# Sheet1.net
KiCad netlist of a schematic drawn in Altium Designer
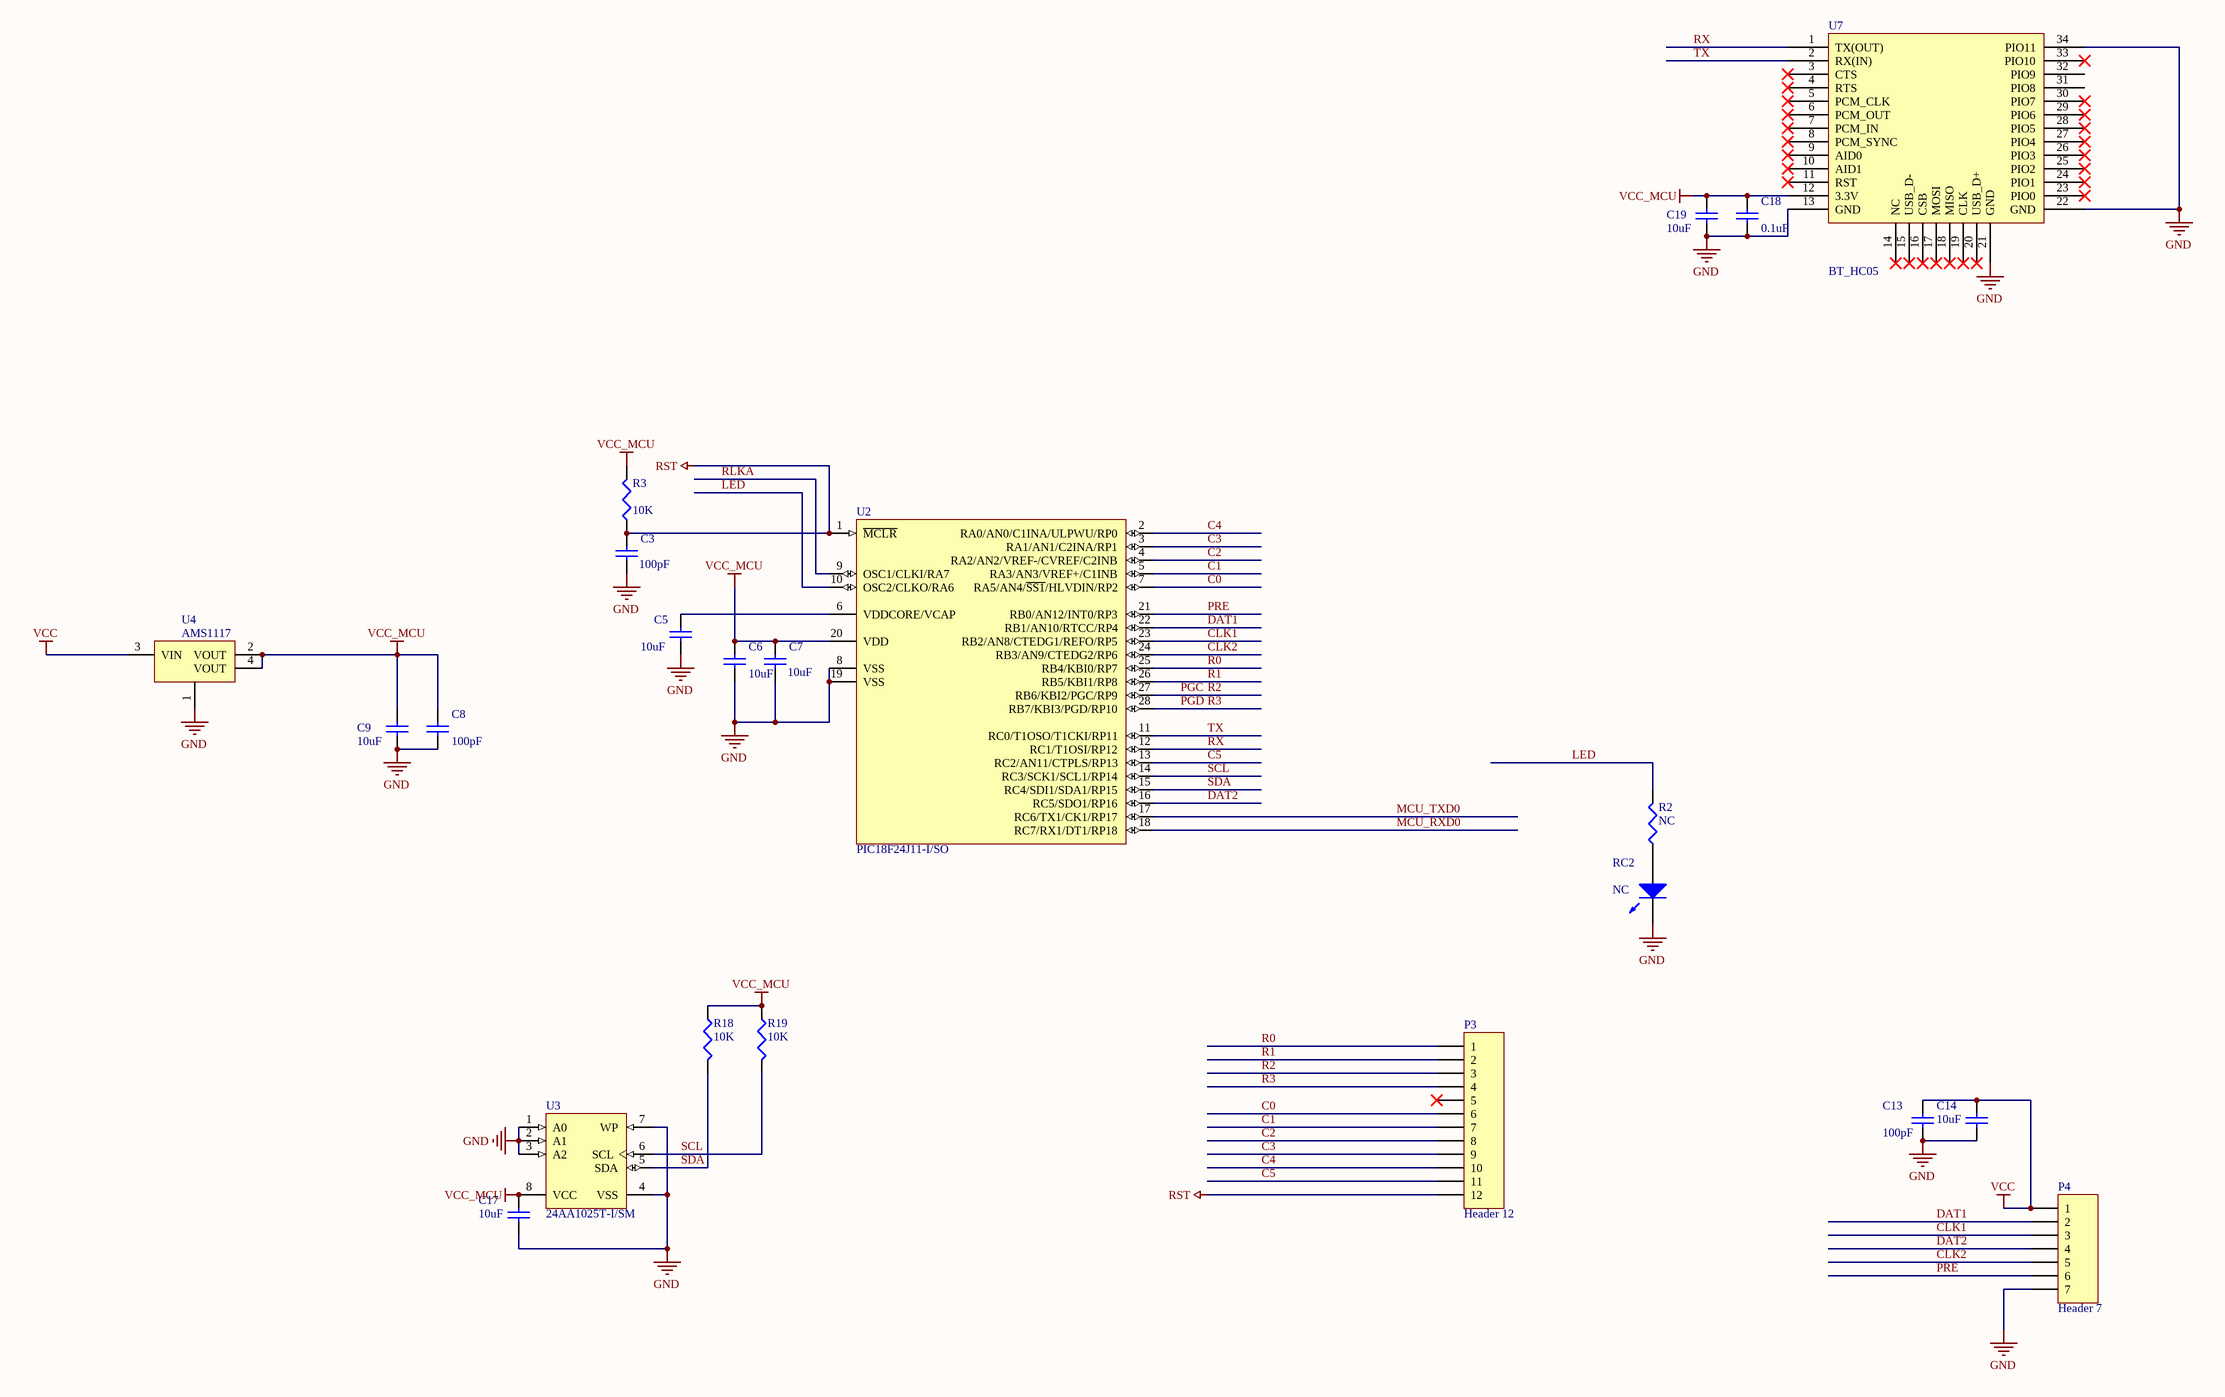
[diagram p0: Sheet1.SchDoc]

(export (version "E")
  (design (tool "Eeschema 10.0.6"))
  (components
    (comp (ref "C3")
      (value "100pF")
      (footprint "CAPC2013X05N")
      (description "0.10µF 50V Ceramic Capacitor Y5V (F) 0805 (2012 Metric) 0.079\" L x 0.049\" W (2.00mm x 1.25mm)")
      (fields (field (name "Comment") "CL21F104ZBCNNNC"))
      (libsource (lib "Miscellaneous Devices") (part "Cap Semi"))
    )
    (comp (ref "C5")
      (value "10uF")
      (footprint "CAPC2013X05N")
      (description "10µF 6.3V Ceramic Capacitor X5R 0805 (2012 Metric) 0.079\" L x 0.049\" W (2.00mm x 1.25mm)")
      (fields (field (name "Comment") "GRM219R60J106KE19D"))
      (libsource (lib "Miscellaneous Devices") (part "Cap Semi"))
    )
    (comp (ref "C6")
      (value "10uF")
      (footprint "CAPC2013X05N")
      (description "10µF 6.3V Ceramic Capacitor X5R 0805 (2012 Metric) 0.079\" L x 0.049\" W (2.00mm x 1.25mm)")
      (fields (field (name "Comment") "GRM219R60J106KE19D"))
      (libsource (lib "Miscellaneous Devices") (part "Cap Semi"))
    )
    (comp (ref "C7")
      (value "10uF")
      (footprint "CAPC2013X05N")
      (description "0.10µF 50V Cera2012 Metric) 0.079\" L x 0.049\" W (2.00mm x 1.25mm)")
      (fields (field (name "Comment") "GRM219R60J106KE19D"))
      (libsource (lib "Miscellaneous Devices") (part "Cap Semi"))
    )
    (comp (ref "C8")
      (value "100pF")
      (footprint "RESC2012L")
      (description "0.10µF 50V Ceramic Capacitor Y5V (F) 0805 (2012 Metric) 0.079\" L x 0.049\" W (2.00mm x 1.25mm)")
      (fields (field (name "Comment") "CL21F104ZBCNNNC"))
      (libsource (lib "Miscellaneous Devices") (part "Cap"))
    )
    (comp (ref "C9")
      (value "10uF")
      (footprint "RESC2012L")
      (description "10µF 6.3V Ceramic Capacitor X5R 0805 (2012 Metric) 0.079\" L x 0.049\" W (2.00mm x 1.25mm)")
      (fields (field (name "Comment") "GRM219R60J106KE19D"))
      (libsource (lib "Miscellaneous Devices") (part "Cap"))
    )
    (comp (ref "C13")
      (value "100pF")
      (footprint "RESC2012L")
      (description "0.10µF 50V Ceramic Capacitor Y5V (F) 0805 (2012 Metric) 0.079\" L x 0.049\" W (2.00mm x 1.25mm)")
      (fields (field (name "Comment") "CL21F104ZBCNNNC"))
      (libsource (lib "Miscellaneous Devices") (part "Cap"))
    )
    (comp (ref "C14")
      (value "10uF")
      (footprint "RESC2012L")
      (description "10µF 6.3V Ceramic Capacitor X5R 0805 (2012 Metric) 0.079\" L x 0.049\" W (2.00mm x 1.25mm)")
      (fields (field (name "Comment") "GRM219R60J106KE19D"))
      (libsource (lib "Miscellaneous Devices") (part "Cap"))
    )
    (comp (ref "C17")
      (value "10uF")
      (footprint "RESC2012L")
      (description "10µF 6.3V Ceramic Capacitor X5R 0805 (2012 Metric) 0.079\" L x 0.049\" W (2.00mm x 1.25mm)")
      (fields (field (name "Comment") "GRM219R60J106KE19D"))
      (libsource (lib "Miscellaneous Devices") (part "Cap"))
    )
    (comp (ref "C18")
      (value "0.1uF")
      (footprint "RESC2012L")
      (description "CAP CER 0.1UF 50V Y5V 0805")
      (fields (field (name "Comment") "CL21F104ZBCNNNC") (field (name "PUBLISHER") "Altium Limited"))
      (libsource (lib "Miscellaneous Devices") (part "Cap"))
    )
    (comp (ref "C19")
      (value "10uF")
      (footprint "RESC2012L")
      (description "CAP CER 10UF 10V Y5V 0805")
      (fields (field (name "Comment") "LMK212F106ZG-T") (field (name "PUBLISHER") "Altium Limited"))
      (libsource (lib "Miscellaneous Devices") (part "Cap"))
    )
    (comp (ref "P3")
      (value "Header 12")
      (footprint "HDR1X12")
      (description "Header, 12-Pin")
      (fields (field (name "PUBLISHER") "Altium Limited"))
      (libsource (lib "Miscellaneous Connectors") (part "Header 12"))
    )
    (comp (ref "P4")
      (value "Header 7")
      (footprint "HDR1X7")
      (description "Header, 7-Pin")
      (fields (field (name "PUBLISHER") "Altium Limited"))
      (libsource (lib "Miscellaneous Connectors") (part "Header 7"))
    )
    (comp (ref "R2")
      (value "NC")
      (footprint "RESC2012L")
      (fields (field (name "PUBLISHER") "Altium Limited"))
      (libsource (lib "Miscellaneous Devices") (part "Res3"))
    )
    (comp (ref "R3")
      (value "10K")
      (footprint "RESC2013X05N")
      (description "RES SMD 10K OHM 5% 1/8W 0805")
      (fields (field (name "Comment") "ERJ-6GEYJ103V"))
      (libsource (lib "Miscellaneous Devices") (part "Res3"))
    )
    (comp (ref "R18")
      (value "10K")
      (footprint "RESC2012L")
      (description "RES SMD 10K OHM 5% 1/8W 0805")
      (fields (field (name "Comment") "ERJ-6GEYJ103V"))
      (libsource (lib "Miscellaneous Devices") (part "Res3"))
    )
    (comp (ref "R19")
      (value "10K")
      (footprint "RESC2012L")
      (description "RES SMD 10K OHM 5% 1/8W 0805")
      (fields (field (name "Comment") "ERJ-6GEYJ103V"))
      (libsource (lib "Miscellaneous Devices") (part "Res3"))
    )
    (comp (ref "RC2")
      (value "NC")
      (footprint "CD3216-1206")
      (description "LED BLUE THRU BOARD 1206")
      (libsource (lib "AM335X_ZCZ") (part "LEDRED1206"))
    )
    (comp (ref "U2")
      (value "PIC18F24J11-I/SO")
      (footprint "SOIC-SO28_N")
      (fields (field (name "PUBLISHER") "Altium Limited"))
      (libsource (lib "Microchip Microcontroller 8-Bit PIC18") (part "PIC18F24J11-I/SO"))
    )
    (comp (ref "U3")
      (value "24AA1025T-I/SM")
      (footprint "SOIJ-SM8_N")
      (description "1 Mbit, 400kHz, 1.7V, I2C Serial EEPROM, 8-Pin SOIC 208mil, Industrial Temperature, Tape and Reel")
      (fields (field (name "PUBLISHER") "Altium Limited"))
      (libsource (lib "Microchip Memory I2C Serial EEPROM") (part "24AA1025T-I/SM"))
    )
    (comp (ref "U4")
      (value "AMS1117")
      (footprint "SOT223-4M")
      (description "Adjustable Precision Shunt Regulator")
      (fields (field (name "PUBLISHER") "Altium Limited"))
      (libsource (lib "Schlib1") (part "AMS1117"))
    )
    (comp (ref "U7")
      (value "BT_HC05")
      (footprint "bluetooth_HC05")
      (libsource (lib "Schlib1") (part "BT_HC05"))
    )
  )
  (nets
    (net (code "1") (name "/C0") (class "Default")
      (node (ref "P3") (pin "6") (pinfunction "6_6") (pintype "passive"))
      (node (ref "U2") (pin "7") (pinfunction "RA5/AN4/~{SS1}/HLVDIN/RP2_7") (pintype "bidirectional"))
    )
    (net (code "2") (name "/C1") (class "Default")
      (node (ref "P3") (pin "7") (pinfunction "7_7") (pintype "passive"))
      (node (ref "U2") (pin "5") (pinfunction "RA3/AN3/VREF+/C1INB_5") (pintype "bidirectional"))
    )
    (net (code "3") (name "/C2") (class "Default")
      (node (ref "P3") (pin "8") (pinfunction "8_8") (pintype "passive"))
      (node (ref "U2") (pin "4") (pinfunction "RA2/AN2/VREF-/CVREF/C2INB_4") (pintype "bidirectional"))
    )
    (net (code "4") (name "/C3") (class "Default")
      (node (ref "P3") (pin "9") (pinfunction "9_9") (pintype "passive"))
      (node (ref "U2") (pin "3") (pinfunction "RA1/AN1/C2INA/RP1_3") (pintype "bidirectional"))
    )
    (net (code "5") (name "/C4") (class "Default")
      (node (ref "P3") (pin "10") (pinfunction "10_10") (pintype "passive"))
      (node (ref "U2") (pin "2") (pinfunction "RA0/AN0/C1INA/ULPWU/RP0_2") (pintype "bidirectional"))
    )
    (net (code "6") (name "/C5") (class "Default")
      (node (ref "P3") (pin "11") (pinfunction "11_11") (pintype "passive"))
      (node (ref "U2") (pin "13") (pinfunction "RC2/AN11/CTPLS/RP13_13") (pintype "bidirectional"))
    )
    (net (code "7") (name "/CLK1") (class "Default")
      (node (ref "P4") (pin "3") (pinfunction "3_3") (pintype "passive"))
      (node (ref "U2") (pin "23") (pinfunction "RB2/AN8/CTEDG1/REFO/RP5_23") (pintype "bidirectional"))
    )
    (net (code "8") (name "/CLK2") (class "Default")
      (node (ref "P4") (pin "5") (pinfunction "5_5") (pintype "passive"))
      (node (ref "U2") (pin "24") (pinfunction "RB3/AN9/CTEDG2/RP6_24") (pintype "bidirectional"))
    )
    (net (code "9") (name "/DAT1") (class "Default")
      (node (ref "P4") (pin "2") (pinfunction "2_2") (pintype "passive"))
      (node (ref "U2") (pin "22") (pinfunction "RB1/AN10/RTCC/RP4_22") (pintype "bidirectional"))
    )
    (net (code "10") (name "/DAT2") (class "Default")
      (node (ref "P4") (pin "4") (pinfunction "4_4") (pintype "passive"))
      (node (ref "U2") (pin "16") (pinfunction "RC5/SDO1/RP16_16") (pintype "bidirectional"))
    )
    (net (code "11") (name "/LED") (class "Default")
      (node (ref "R2") (pin "1") (pinfunction "1_1") (pintype "passive"))
      (node (ref "U2") (pin "10") (pinfunction "OSC2/CLKO/RA6_10") (pintype "bidirectional"))
    )
    (net (code "12") (name "/MCU_RXD0") (class "Default")
      (node (ref "U2") (pin "18") (pinfunction "RC7/RX1/DT1/RP18_18") (pintype "bidirectional"))
    )
    (net (code "13") (name "/MCU_TXD0") (class "Default")
      (node (ref "U2") (pin "17") (pinfunction "RC6/TX1/CK1/RP17_17") (pintype "bidirectional"))
    )
    (net (code "14") (name "/PGC") (class "Default")
      (node (ref "P3") (pin "3") (pinfunction "3_3") (pintype "passive"))
      (node (ref "U2") (pin "27") (pinfunction "RB6/KBI2/PGC/RP9_27") (pintype "bidirectional"))
    )
    (net (code "15") (name "/PGD") (class "Default")
      (node (ref "P3") (pin "4") (pinfunction "4_4") (pintype "passive"))
      (node (ref "U2") (pin "28") (pinfunction "RB7/KBI3/PGD/RP10_28") (pintype "bidirectional"))
    )
    (net (code "16") (name "/PRE") (class "Default")
      (node (ref "P4") (pin "6") (pinfunction "6_6") (pintype "passive"))
      (node (ref "U2") (pin "21") (pinfunction "RB0/AN12/INT0/RP3_21") (pintype "bidirectional"))
    )
    (net (code "17") (name "/R0") (class "Default")
      (node (ref "P3") (pin "1") (pinfunction "1_1") (pintype "passive"))
      (node (ref "U2") (pin "25") (pinfunction "RB4/KBI0/RP7_25") (pintype "bidirectional"))
    )
    (net (code "18") (name "/R1") (class "Default")
      (node (ref "P3") (pin "2") (pinfunction "2_2") (pintype "passive"))
      (node (ref "U2") (pin "26") (pinfunction "RB5/KBI1/RP8_26") (pintype "bidirectional"))
    )
    (net (code "19") (name "/RLKA") (class "Default")
      (node (ref "U2") (pin "9") (pinfunction "OSC1/CLKI/RA7_9") (pintype "bidirectional"))
    )
    (net (code "20") (name "/RX") (class "Default")
      (node (ref "U2") (pin "12") (pinfunction "RC1/T1OSI/RP12_12") (pintype "bidirectional"))
      (node (ref "U7") (pin "1") (pinfunction "TX(OUT)_1") (pintype "passive"))
    )
    (net (code "21") (name "/SCL") (class "Default")
      (node (ref "R19") (pin "1") (pinfunction "1_1") (pintype "passive"))
      (node (ref "U2") (pin "14") (pinfunction "RC3/SCK1/SCL1/RP14_14") (pintype "bidirectional"))
      (node (ref "U3") (pin "6") (pinfunction "SCL_6") (pintype "input"))
    )
    (net (code "22") (name "/SDA") (class "Default")
      (node (ref "R18") (pin "1") (pinfunction "1_1") (pintype "passive"))
      (node (ref "U2") (pin "15") (pinfunction "RC4/SDI1/SDA1/RP15_15") (pintype "bidirectional"))
      (node (ref "U3") (pin "5") (pinfunction "SDA_5") (pintype "bidirectional"))
    )
    (net (code "23") (name "/TX") (class "Default")
      (node (ref "U2") (pin "11") (pinfunction "RC0/T1OSO/T1CKI/RP11_11") (pintype "bidirectional"))
      (node (ref "U7") (pin "2") (pinfunction "RX(IN)_2") (pintype "passive"))
    )
    (net (code "24") (name "GND") (class "Default")
      (node (ref "C13") (pin "2") (pinfunction "2_2") (pintype "passive"))
      (node (ref "C14") (pin "2") (pinfunction "2_2") (pintype "passive"))
      (node (ref "C17") (pin "2") (pinfunction "2_2") (pintype "passive"))
      (node (ref "C18") (pin "2") (pinfunction "2_2") (pintype "passive"))
      (node (ref "C19") (pin "2") (pinfunction "2_2") (pintype "passive"))
      (node (ref "C3") (pin "1") (pinfunction "1_1") (pintype "passive"))
      (node (ref "C5") (pin "1") (pinfunction "1_1") (pintype "passive"))
      (node (ref "C6") (pin "1") (pinfunction "1_1") (pintype "passive"))
      (node (ref "C7") (pin "1") (pinfunction "1_1") (pintype "passive"))
      (node (ref "C8") (pin "2") (pinfunction "2_2") (pintype "passive"))
      (node (ref "C9") (pin "2") (pinfunction "2_2") (pintype "passive"))
      (node (ref "P4") (pin "7") (pinfunction "7_7") (pintype "passive"))
      (node (ref "RC2") (pin "2") (pinfunction "K_2") (pintype "passive"))
      (node (ref "U2") (pin "19") (pinfunction "VSS_19") (pintype "power_in"))
      (node (ref "U2") (pin "8") (pinfunction "VSS_8") (pintype "power_in"))
      (node (ref "U3") (pin "1") (pinfunction "A0_1") (pintype "input"))
      (node (ref "U3") (pin "2") (pinfunction "A1_2") (pintype "input"))
      (node (ref "U3") (pin "3") (pinfunction "A2_3") (pintype "input"))
      (node (ref "U3") (pin "4") (pinfunction "VSS_4") (pintype "power_in"))
      (node (ref "U3") (pin "7") (pinfunction "WP_7") (pintype "input"))
      (node (ref "U4") (pin "1") (pinfunction "GND_1") (pintype "power_in"))
      (node (ref "U7") (pin "13") (pinfunction "GND_13") (pintype "passive"))
      (node (ref "U7") (pin "21") (pinfunction "GND_21") (pintype "passive"))
      (node (ref "U7") (pin "22") (pinfunction "GND_22") (pintype "passive"))
      (node (ref "U7") (pin "34") (pinfunction "PIO11_34") (pintype "passive"))
    )
    (net (code "25") (name "Net-(RC2-A)") (class "Default")
      (node (ref "R2") (pin "2") (pinfunction "2_2") (pintype "passive"))
      (node (ref "RC2") (pin "1") (pinfunction "A_1") (pintype "passive"))
    )
    (net (code "26") (name "Net-(U2-VDDCORE{slash}VCAP)") (class "Default")
      (node (ref "C5") (pin "2") (pinfunction "2_2") (pintype "passive"))
      (node (ref "U2") (pin "6") (pinfunction "VDDCORE/VCAP_6") (pintype "power_in"))
    )
    (net (code "27") (name "RST") (class "Default")
      (node (ref "C3") (pin "2") (pinfunction "2_2") (pintype "passive"))
      (node (ref "P3") (pin "12") (pinfunction "12_12") (pintype "passive"))
      (node (ref "R3") (pin "1") (pinfunction "1_1") (pintype "passive"))
      (node (ref "U2") (pin "1") (pinfunction "~{MCLR}_1") (pintype "input"))
    )
    (net (code "28") (name "VCC") (class "Default")
      (node (ref "C13") (pin "1") (pinfunction "1_1") (pintype "passive"))
      (node (ref "C14") (pin "1") (pinfunction "1_1") (pintype "passive"))
      (node (ref "P4") (pin "1") (pinfunction "1_1") (pintype "passive"))
      (node (ref "U4") (pin "3") (pinfunction "VIN_3") (pintype "power_in"))
    )
    (net (code "29") (name "VCC_MCU") (class "Default")
      (node (ref "C17") (pin "1") (pinfunction "1_1") (pintype "passive"))
      (node (ref "C18") (pin "1") (pinfunction "1_1") (pintype "passive"))
      (node (ref "C19") (pin "1") (pinfunction "1_1") (pintype "passive"))
      (node (ref "C6") (pin "2") (pinfunction "2_2") (pintype "passive"))
      (node (ref "C7") (pin "2") (pinfunction "2_2") (pintype "passive"))
      (node (ref "C8") (pin "1") (pinfunction "1_1") (pintype "passive"))
      (node (ref "C9") (pin "1") (pinfunction "1_1") (pintype "passive"))
      (node (ref "R18") (pin "2") (pinfunction "2_2") (pintype "passive"))
      (node (ref "R19") (pin "2") (pinfunction "2_2") (pintype "passive"))
      (node (ref "R3") (pin "2") (pinfunction "2_2") (pintype "passive"))
      (node (ref "U2") (pin "20") (pinfunction "VDD_20") (pintype "power_in"))
      (node (ref "U3") (pin "8") (pinfunction "VCC_8") (pintype "power_in"))
      (node (ref "U4") (pin "2") (pinfunction "VOUT_2") (pintype "power_in"))
      (node (ref "U4") (pin "4") (pinfunction "VOUT_4") (pintype "power_in"))
      (node (ref "U7") (pin "12") (pinfunction "3.3V_12") (pintype "passive"))
    )
    (net (code "30") (name "unconnected-(P3-Pad5)") (class "Default")
      (node (ref "P3") (pin "5") (pinfunction "5_5") (pintype "passive+no_connect"))
    )
    (net (code "31") (name "unconnected-(U7-AID0-Pad9)") (class "Default")
      (node (ref "U7") (pin "9") (pinfunction "AID0_9") (pintype "passive+no_connect"))
    )
    (net (code "32") (name "unconnected-(U7-AID1-Pad10)") (class "Default")
      (node (ref "U7") (pin "10") (pinfunction "AID1_10") (pintype "passive+no_connect"))
    )
    (net (code "33") (name "unconnected-(U7-CLK-Pad19)") (class "Default")
      (node (ref "U7") (pin "19") (pinfunction "CLK_19") (pintype "passive+no_connect"))
    )
    (net (code "34") (name "unconnected-(U7-CSB-Pad16)") (class "Default")
      (node (ref "U7") (pin "16") (pinfunction "CSB_16") (pintype "passive+no_connect"))
    )
    (net (code "35") (name "unconnected-(U7-CTS-Pad3)") (class "Default")
      (node (ref "U7") (pin "3") (pinfunction "CTS_3") (pintype "passive+no_connect"))
    )
    (net (code "36") (name "unconnected-(U7-MISO-Pad18)") (class "Default")
      (node (ref "U7") (pin "18") (pinfunction "MISO_18") (pintype "passive+no_connect"))
    )
    (net (code "37") (name "unconnected-(U7-MOSI-Pad17)") (class "Default")
      (node (ref "U7") (pin "17") (pinfunction "MOSI_17") (pintype "passive+no_connect"))
    )
    (net (code "38") (name "unconnected-(U7-NC-Pad14)") (class "Default")
      (node (ref "U7") (pin "14") (pinfunction "NC_14") (pintype "passive+no_connect"))
    )
    (net (code "39") (name "unconnected-(U7-PCM_CLK-Pad5)") (class "Default")
      (node (ref "U7") (pin "5") (pinfunction "PCM_CLK_5") (pintype "passive+no_connect"))
    )
    (net (code "40") (name "unconnected-(U7-PCM_IN-Pad7)") (class "Default")
      (node (ref "U7") (pin "7") (pinfunction "PCM_IN_7") (pintype "passive+no_connect"))
    )
    (net (code "41") (name "unconnected-(U7-PCM_OUT-Pad6)") (class "Default")
      (node (ref "U7") (pin "6") (pinfunction "PCM_OUT_6") (pintype "passive+no_connect"))
    )
    (net (code "42") (name "unconnected-(U7-PCM_SYNC-Pad8)") (class "Default")
      (node (ref "U7") (pin "8") (pinfunction "PCM_SYNC_8") (pintype "passive+no_connect"))
    )
    (net (code "43") (name "unconnected-(U7-PIO0-Pad23)") (class "Default")
      (node (ref "U7") (pin "23") (pinfunction "PIO0_23") (pintype "passive+no_connect"))
    )
    (net (code "44") (name "unconnected-(U7-PIO1-Pad24)") (class "Default")
      (node (ref "U7") (pin "24") (pinfunction "PIO1_24") (pintype "passive+no_connect"))
    )
    (net (code "45") (name "unconnected-(U7-PIO2-Pad25)") (class "Default")
      (node (ref "U7") (pin "25") (pinfunction "PIO2_25") (pintype "passive+no_connect"))
    )
    (net (code "46") (name "unconnected-(U7-PIO3-Pad26)") (class "Default")
      (node (ref "U7") (pin "26") (pinfunction "PIO3_26") (pintype "passive+no_connect"))
    )
    (net (code "47") (name "unconnected-(U7-PIO4-Pad27)") (class "Default")
      (node (ref "U7") (pin "27") (pinfunction "PIO4_27") (pintype "passive+no_connect"))
    )
    (net (code "48") (name "unconnected-(U7-PIO5-Pad28)") (class "Default")
      (node (ref "U7") (pin "28") (pinfunction "PIO5_28") (pintype "passive+no_connect"))
    )
    (net (code "49") (name "unconnected-(U7-PIO6-Pad29)") (class "Default")
      (node (ref "U7") (pin "29") (pinfunction "PIO6_29") (pintype "passive+no_connect"))
    )
    (net (code "50") (name "unconnected-(U7-PIO7-Pad30)") (class "Default")
      (node (ref "U7") (pin "30") (pinfunction "PIO7_30") (pintype "passive+no_connect"))
    )
    (net (code "51") (name "unconnected-(U7-PIO8-Pad31)") (class "Default")
      (node (ref "U7") (pin "31") (pinfunction "PIO8_31") (pintype "passive"))
    )
    (net (code "52") (name "unconnected-(U7-PIO9-Pad32)") (class "Default")
      (node (ref "U7") (pin "32") (pinfunction "PIO9_32") (pintype "passive"))
    )
    (net (code "53") (name "unconnected-(U7-PIO10-Pad33)") (class "Default")
      (node (ref "U7") (pin "33") (pinfunction "PIO10_33") (pintype "passive+no_connect"))
    )
    (net (code "54") (name "unconnected-(U7-RST-Pad11)") (class "Default")
      (node (ref "U7") (pin "11") (pinfunction "RST_11") (pintype "passive+no_connect"))
    )
    (net (code "55") (name "unconnected-(U7-RTS-Pad4)") (class "Default")
      (node (ref "U7") (pin "4") (pinfunction "RTS_4") (pintype "passive+no_connect"))
    )
    (net (code "56") (name "unconnected-(U7-USB_D+-Pad20)") (class "Default")
      (node (ref "U7") (pin "20") (pinfunction "USB_D+_20") (pintype "passive+no_connect"))
    )
    (net (code "57") (name "unconnected-(U7-USB_D--Pad15)") (class "Default")
      (node (ref "U7") (pin "15") (pinfunction "USB_D-_15") (pintype "passive+no_connect"))
    )
  )
)
